# BrainA2-B-11Nov2014.net
KiCad netlist of a schematic drawn in EAGLE
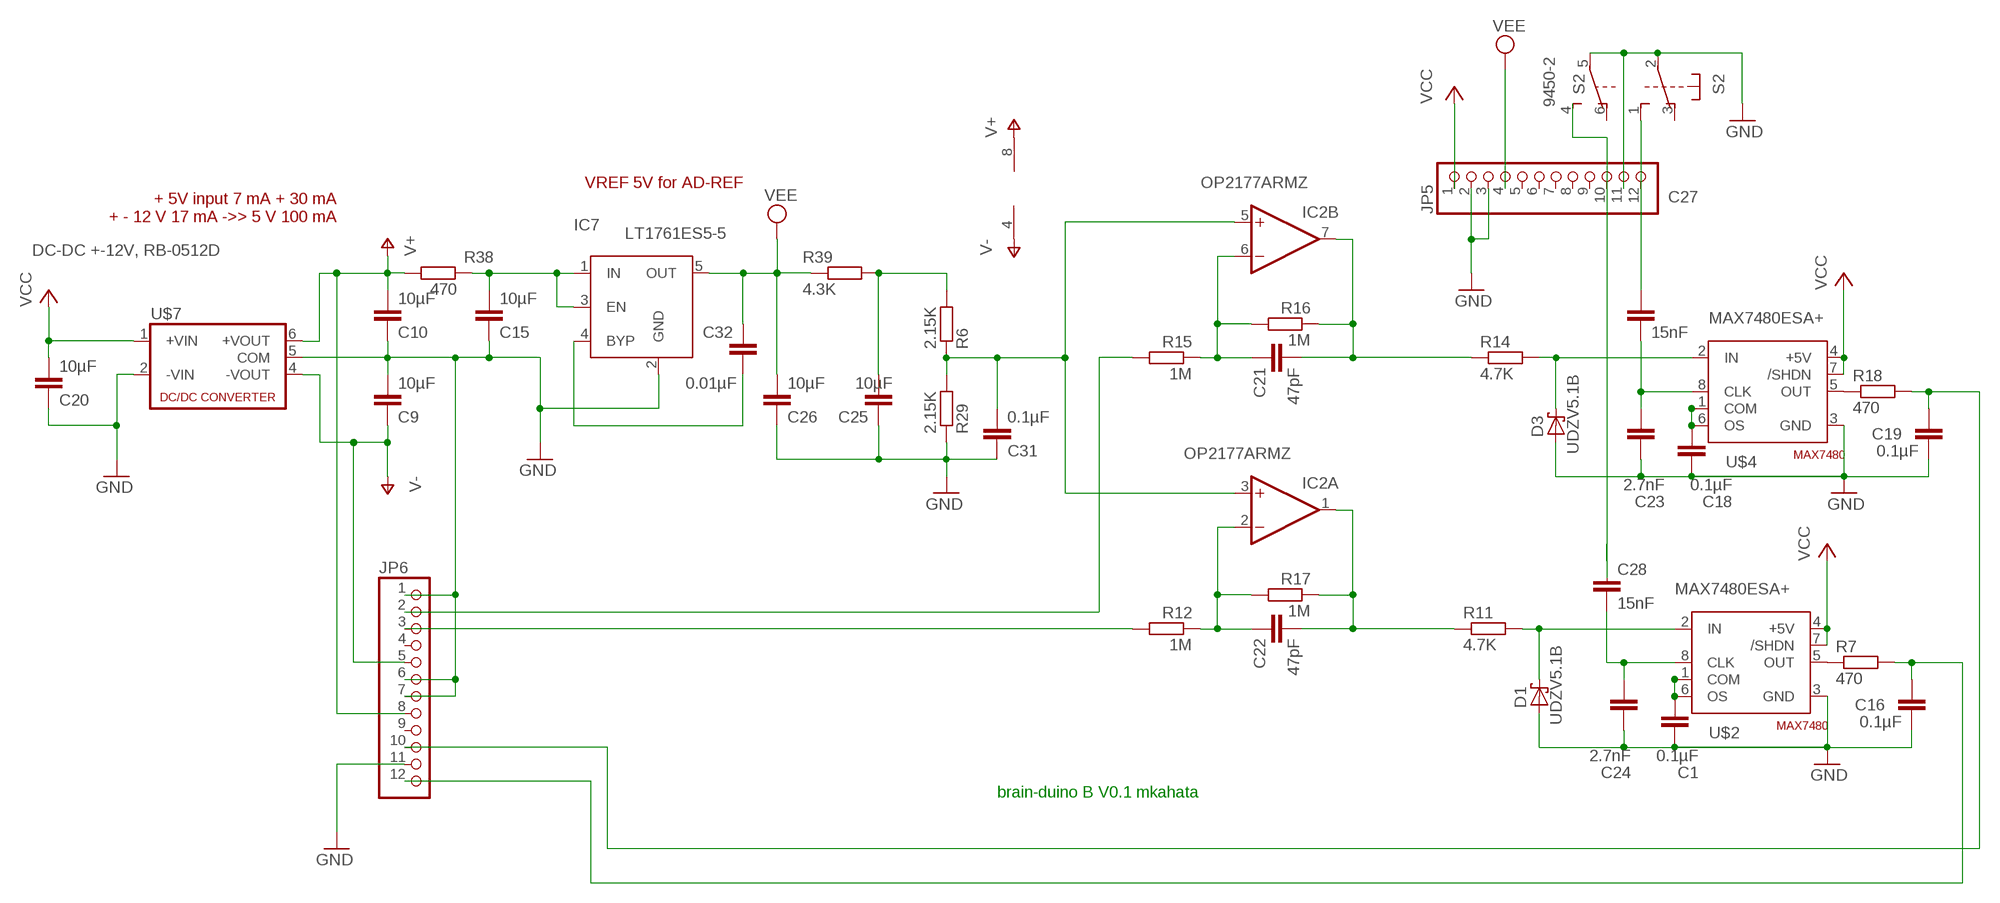
[diagram p0: schematic, sheet 1]

(export (version "E")
  (design (tool "Eeschema 10.0.6"))
  (components
    (comp (ref "C1")
      (value "0.1µF")
      (footprint "eagle-import:C0603")
      (libsource (lib "eagle-import") (part "C-EUC0603"))
    )
    (comp (ref "C9")
      (value "10µF")
      (footprint "eagle-import:C0603")
      (libsource (lib "eagle-import") (part "C-EUC0603"))
    )
    (comp (ref "C10")
      (value "10µF")
      (footprint "eagle-import:C0603")
      (libsource (lib "eagle-import") (part "C-EUC0603"))
    )
    (comp (ref "C15")
      (value "10µF")
      (footprint "eagle-import:C0603")
      (libsource (lib "eagle-import") (part "C-EUC0603"))
    )
    (comp (ref "C16")
      (value "0.1µF")
      (footprint "eagle-import:C0603")
      (libsource (lib "eagle-import") (part "C-EUC0603"))
    )
    (comp (ref "C18")
      (value "0.1µF")
      (footprint "eagle-import:C0603")
      (libsource (lib "eagle-import") (part "C-EUC0603"))
    )
    (comp (ref "C19")
      (value "0.1µF")
      (footprint "eagle-import:C0603")
      (libsource (lib "eagle-import") (part "C-EUC0603"))
    )
    (comp (ref "C20")
      (value "10µF")
      (footprint "eagle-import:C0603")
      (libsource (lib "eagle-import") (part "C-EUC0603"))
    )
    (comp (ref "C21")
      (value "47pF")
      (footprint "eagle-import:C0603")
      (libsource (lib "eagle-import") (part "C-EUC0603"))
    )
    (comp (ref "C22")
      (value "47pF")
      (footprint "eagle-import:C0603")
      (libsource (lib "eagle-import") (part "C-EUC0603"))
    )
    (comp (ref "C23")
      (value "2.7nF")
      (footprint "eagle-import:C0603")
      (libsource (lib "eagle-import") (part "C-EUC0603"))
    )
    (comp (ref "C24")
      (value "2.7nF")
      (footprint "eagle-import:C0603")
      (libsource (lib "eagle-import") (part "C-EUC0603"))
    )
    (comp (ref "C25")
      (value "10µF")
      (footprint "eagle-import:C0603")
      (libsource (lib "eagle-import") (part "C-EUC0603"))
    )
    (comp (ref "C26")
      (value "10µF")
      (footprint "eagle-import:C0603")
      (libsource (lib "eagle-import") (part "C-EUC0603"))
    )
    (comp (ref "C27")
      (value "15nF")
      (footprint "eagle-import:C0603")
      (libsource (lib "eagle-import") (part "C-EUC0603"))
    )
    (comp (ref "C28")
      (value "15nF")
      (footprint "eagle-import:C0603")
      (libsource (lib "eagle-import") (part "C-EUC0603"))
    )
    (comp (ref "C31")
      (value "0.1µF")
      (footprint "eagle-import:C0603")
      (libsource (lib "eagle-import") (part "C-EUC0603"))
    )
    (comp (ref "C32")
      (value "0.01µF")
      (footprint "eagle-import:C0603")
      (libsource (lib "eagle-import") (part "C-EUC0603"))
    )
    (comp (ref "D1")
      (value "UDZV5.1B")
      (footprint "eagle-import:SOD323_ST")
      (libsource (lib "eagle-import") (part "BAT60J"))
    )
    (comp (ref "D3")
      (value "UDZV5.1B")
      (footprint "eagle-import:SOD323_ST")
      (libsource (lib "eagle-import") (part "BAT60J"))
    )
    (comp (ref "IC2")
      (value "OP2177ARMZ")
      (footprint "eagle-import:MSOP08")
      (libsource (lib "eagle-import") (part "OP1277RM"))
    )
    (comp (ref "IC7")
      (value "LT1761ES5-5")
      (footprint "eagle-import:SOT23-5")
      (libsource (lib "eagle-import") (part "MIC5219XX"))
    )
    (comp (ref "JP5")
      (value "PINHD-1X12")
      (footprint "eagle-import:1X12")
      (libsource (lib "eagle-import") (part "PINHD-1X12"))
    )
    (comp (ref "JP6")
      (value "PINHD-1X12")
      (footprint "eagle-import:1X12")
      (libsource (lib "eagle-import") (part "PINHD-1X12"))
    )
    (comp (ref "R6")
      (value "2.15K")
      (footprint "eagle-import:R0603")
      (libsource (lib "eagle-import") (part "R-EU_R0603"))
    )
    (comp (ref "R7")
      (value "470")
      (footprint "eagle-import:R0603")
      (libsource (lib "eagle-import") (part "R-EU_R0603"))
    )
    (comp (ref "R11")
      (value "4.7K")
      (footprint "eagle-import:R0603")
      (libsource (lib "eagle-import") (part "R-EU_R0603"))
    )
    (comp (ref "R12")
      (value "1M")
      (footprint "eagle-import:R0603")
      (libsource (lib "eagle-import") (part "R-EU_R0603"))
    )
    (comp (ref "R14")
      (value "4.7K")
      (footprint "eagle-import:R0603")
      (libsource (lib "eagle-import") (part "R-EU_R0603"))
    )
    (comp (ref "R15")
      (value "1M")
      (footprint "eagle-import:R0603")
      (libsource (lib "eagle-import") (part "R-EU_R0603"))
    )
    (comp (ref "R16")
      (value "1M")
      (footprint "eagle-import:R0603")
      (libsource (lib "eagle-import") (part "R-EU_R0603"))
    )
    (comp (ref "R17")
      (value "1M")
      (footprint "eagle-import:R0603")
      (libsource (lib "eagle-import") (part "R-EU_R0603"))
    )
    (comp (ref "R18")
      (value "470")
      (footprint "eagle-import:R0603")
      (libsource (lib "eagle-import") (part "R-EU_R0603"))
    )
    (comp (ref "R29")
      (value "2.15K")
      (footprint "eagle-import:R0603")
      (libsource (lib "eagle-import") (part "R-EU_R0603"))
    )
    (comp (ref "R38")
      (value "470")
      (footprint "eagle-import:R0603")
      (libsource (lib "eagle-import") (part "R-EU_R0603"))
    )
    (comp (ref "R39")
      (value "4.3K")
      (footprint "eagle-import:R0603")
      (libsource (lib "eagle-import") (part "R-EU_R0603"))
    )
    (comp (ref "S2")
      (value "9450-2")
      (footprint "eagle-import:9450-2")
      (libsource (lib "eagle-import") (part "9450-2"))
    )
    (comp (ref "U$2")
      (value "MAX7480ESA+")
      (footprint "eagle-import:MAX7480")
      (libsource (lib "eagle-import") (part "MAX7480"))
    )
    (comp (ref "U$4")
      (value "MAX7480ESA+")
      (footprint "eagle-import:MAX7480")
      (libsource (lib "eagle-import") (part "MAX7480"))
    )
    (comp (ref "U$7")
      (value "DC-DC +-12V, RB-0512D")
      (footprint "eagle-import:RB-0515D")
      (libsource (lib "eagle-import") (part "RB-0515D"))
    )
  )
  (nets
    (net (code "1") (name "GND") (class "Default")
      (node (ref "C1") (pin "1") (pinfunction "1_1") (pintype "passive"))
      (node (ref "C10") (pin "1") (pinfunction "1_1") (pintype "passive"))
      (node (ref "C15") (pin "1") (pinfunction "1_1") (pintype "passive"))
      (node (ref "C16") (pin "1") (pinfunction "1_1") (pintype "passive"))
      (node (ref "C18") (pin "1") (pinfunction "1_1") (pintype "passive"))
      (node (ref "C19") (pin "1") (pinfunction "1_1") (pintype "passive"))
      (node (ref "C20") (pin "1") (pinfunction "1_1") (pintype "passive"))
      (node (ref "C23") (pin "1") (pinfunction "1_1") (pintype "passive"))
      (node (ref "C24") (pin "1") (pinfunction "1_1") (pintype "passive"))
      (node (ref "C25") (pin "1") (pinfunction "1_1") (pintype "passive"))
      (node (ref "C26") (pin "1") (pinfunction "1_1") (pintype "passive"))
      (node (ref "C31") (pin "1") (pinfunction "1_1") (pintype "passive"))
      (node (ref "C9") (pin "2") (pinfunction "2_2") (pintype "passive"))
      (node (ref "D1") (pin "A") (pinfunction "A_A") (pintype "passive"))
      (node (ref "D3") (pin "A") (pinfunction "A_A") (pintype "passive"))
      (node (ref "IC7") (pin "2") (pinfunction "GND_2") (pintype "power_in"))
      (node (ref "JP5") (pin "11") (pinfunction "11_11") (pintype "passive"))
      (node (ref "JP5") (pin "2") (pinfunction "2_2") (pintype "passive"))
      (node (ref "JP5") (pin "3") (pinfunction "3_3") (pintype "passive"))
      (node (ref "JP6") (pin "1") (pinfunction "1_1") (pintype "passive"))
      (node (ref "JP6") (pin "11") (pinfunction "11_11") (pintype "passive"))
      (node (ref "JP6") (pin "6") (pinfunction "6_6") (pintype "passive"))
      (node (ref "JP6") (pin "7") (pinfunction "7_7") (pintype "passive"))
      (node (ref "R29") (pin "1") (pinfunction "1_1") (pintype "passive"))
      (node (ref "S2") (pin "2") (pinfunction "P_2") (pintype "passive"))
      (node (ref "S2") (pin "5") (pinfunction "P_5") (pintype "passive"))
      (node (ref "U$2") (pin "3") (pinfunction "GND_3") (pintype "power_in"))
      (node (ref "U$4") (pin "3") (pinfunction "GND_3") (pintype "power_in"))
      (node (ref "U$7") (pin "2") (pinfunction "-VIN_2") (pintype "passive"))
      (node (ref "U$7") (pin "5") (pinfunction "COM_5") (pintype "passive"))
    )
    (net (code "2") (name "Net-(C16-Pad2)") (class "Default")
      (node (ref "C16") (pin "2") (pinfunction "2_2") (pintype "passive"))
      (node (ref "JP6") (pin "12") (pinfunction "12_12") (pintype "passive"))
      (node (ref "R7") (pin "2") (pinfunction "2_2") (pintype "passive"))
    )
    (net (code "3") (name "Net-(C19-Pad2)") (class "Default")
      (node (ref "C19") (pin "2") (pinfunction "2_2") (pintype "passive"))
      (node (ref "JP6") (pin "10") (pinfunction "10_10") (pintype "passive"))
      (node (ref "R18") (pin "2") (pinfunction "2_2") (pintype "passive"))
    )
    (net (code "4") (name "Net-(C25-Pad2)") (class "Default")
      (node (ref "C25") (pin "2") (pinfunction "2_2") (pintype "passive"))
      (node (ref "R39") (pin "2") (pinfunction "2_2") (pintype "passive"))
      (node (ref "R6") (pin "2") (pinfunction "2_2") (pintype "passive"))
    )
    (net (code "5") (name "Net-(IC2A-+IN)") (class "Default")
      (node (ref "C31") (pin "2") (pinfunction "2_2") (pintype "passive"))
      (node (ref "IC2") (pin "3") (pinfunction "+IN_3") (pintype "input"))
      (node (ref "IC2") (pin "5") (pinfunction "+IN_5") (pintype "input"))
      (node (ref "R29") (pin "2") (pinfunction "2_2") (pintype "passive"))
      (node (ref "R6") (pin "1") (pinfunction "1_1") (pintype "passive"))
    )
    (net (code "6") (name "Net-(IC2A--IN)") (class "Default")
      (node (ref "C22") (pin "1") (pinfunction "1_1") (pintype "passive"))
      (node (ref "IC2") (pin "2") (pinfunction "-IN_2") (pintype "input"))
      (node (ref "R12") (pin "1") (pinfunction "1_1") (pintype "passive"))
      (node (ref "R17") (pin "2") (pinfunction "2_2") (pintype "passive"))
    )
    (net (code "7") (name "Net-(IC2A-OUT)") (class "Default")
      (node (ref "C22") (pin "2") (pinfunction "2_2") (pintype "passive"))
      (node (ref "IC2") (pin "1") (pinfunction "OUT_1") (pintype "output"))
      (node (ref "R11") (pin "1") (pinfunction "1_1") (pintype "passive"))
      (node (ref "R17") (pin "1") (pinfunction "1_1") (pintype "passive"))
    )
    (net (code "8") (name "Net-(IC2B--IN)") (class "Default")
      (node (ref "C21") (pin "1") (pinfunction "1_1") (pintype "passive"))
      (node (ref "IC2") (pin "6") (pinfunction "-IN_6") (pintype "input"))
      (node (ref "R15") (pin "1") (pinfunction "1_1") (pintype "passive"))
      (node (ref "R16") (pin "2") (pinfunction "2_2") (pintype "passive"))
    )
    (net (code "9") (name "Net-(IC2B-OUT)") (class "Default")
      (node (ref "C21") (pin "2") (pinfunction "2_2") (pintype "passive"))
      (node (ref "IC2") (pin "7") (pinfunction "OUT_7") (pintype "output"))
      (node (ref "R14") (pin "1") (pinfunction "1_1") (pintype "passive"))
      (node (ref "R16") (pin "1") (pinfunction "1_1") (pintype "passive"))
    )
    (net (code "10") (name "Net-(IC7-BYP)") (class "Default")
      (node (ref "C32") (pin "1") (pinfunction "1_1") (pintype "passive"))
      (node (ref "IC7") (pin "4") (pinfunction "BYP_4") (pintype "passive"))
    )
    (net (code "11") (name "Net-(IC7-EN)") (class "Default")
      (node (ref "C15") (pin "2") (pinfunction "2_2") (pintype "passive"))
      (node (ref "IC7") (pin "1") (pinfunction "IN_1") (pintype "input"))
      (node (ref "IC7") (pin "3") (pinfunction "EN_3") (pintype "input"))
      (node (ref "R38") (pin "2") (pinfunction "2_2") (pintype "passive"))
    )
    (net (code "12") (name "Net-(JP6-Pad2)") (class "Default")
      (node (ref "JP6") (pin "2") (pinfunction "2_2") (pintype "passive"))
      (node (ref "R15") (pin "2") (pinfunction "2_2") (pintype "passive"))
    )
    (net (code "13") (name "Net-(JP6-Pad3)") (class "Default")
      (node (ref "JP6") (pin "3") (pinfunction "3_3") (pintype "passive"))
      (node (ref "R12") (pin "2") (pinfunction "2_2") (pintype "passive"))
    )
    (net (code "14") (name "Net-(S2A-S)") (class "Default")
      (node (ref "C27") (pin "1") (pinfunction "1_1") (pintype "passive"))
      (node (ref "JP5") (pin "12") (pinfunction "12_12") (pintype "passive"))
      (node (ref "S2") (pin "1") (pinfunction "S_1") (pintype "passive"))
    )
    (net (code "15") (name "Net-(S2B-S)") (class "Default")
      (node (ref "C28") (pin "1") (pinfunction "1_1") (pintype "passive"))
      (node (ref "JP5") (pin "10") (pinfunction "10_10") (pintype "passive"))
      (node (ref "S2") (pin "4") (pinfunction "S_4") (pintype "passive"))
    )
    (net (code "16") (name "Net-(U$2-CLK)") (class "Default")
      (node (ref "C24") (pin "2") (pinfunction "2_2") (pintype "passive"))
      (node (ref "C28") (pin "2") (pinfunction "2_2") (pintype "passive"))
      (node (ref "U$2") (pin "8") (pinfunction "CLK_8") (pintype "input"))
    )
    (net (code "17") (name "Net-(U$2-COM)") (class "Default")
      (node (ref "C1") (pin "2") (pinfunction "2_2") (pintype "passive"))
      (node (ref "U$2") (pin "1") (pinfunction "COM_1") (pintype "input"))
      (node (ref "U$2") (pin "6") (pinfunction "OS_6") (pintype "passive"))
    )
    (net (code "18") (name "Net-(U$2-IN)") (class "Default")
      (node (ref "D1") (pin "C") (pinfunction "C_C") (pintype "passive"))
      (node (ref "R11") (pin "2") (pinfunction "2_2") (pintype "passive"))
      (node (ref "U$2") (pin "2") (pinfunction "IN_2") (pintype "input"))
    )
    (net (code "19") (name "Net-(U$2-OUT)") (class "Default")
      (node (ref "R7") (pin "1") (pinfunction "1_1") (pintype "passive"))
      (node (ref "U$2") (pin "5") (pinfunction "OUT_5") (pintype "input"))
    )
    (net (code "20") (name "Net-(U$4-CLK)") (class "Default")
      (node (ref "C23") (pin "2") (pinfunction "2_2") (pintype "passive"))
      (node (ref "C27") (pin "2") (pinfunction "2_2") (pintype "passive"))
      (node (ref "U$4") (pin "8") (pinfunction "CLK_8") (pintype "input"))
    )
    (net (code "21") (name "Net-(U$4-COM)") (class "Default")
      (node (ref "C18") (pin "2") (pinfunction "2_2") (pintype "passive"))
      (node (ref "U$4") (pin "1") (pinfunction "COM_1") (pintype "input"))
      (node (ref "U$4") (pin "6") (pinfunction "OS_6") (pintype "passive"))
    )
    (net (code "22") (name "Net-(U$4-IN)") (class "Default")
      (node (ref "D3") (pin "C") (pinfunction "C_C") (pintype "passive"))
      (node (ref "R14") (pin "2") (pinfunction "2_2") (pintype "passive"))
      (node (ref "U$4") (pin "2") (pinfunction "IN_2") (pintype "input"))
    )
    (net (code "23") (name "Net-(U$4-OUT)") (class "Default")
      (node (ref "R18") (pin "1") (pinfunction "1_1") (pintype "passive"))
      (node (ref "U$4") (pin "5") (pinfunction "OUT_5") (pintype "input"))
    )
    (net (code "24") (name "V+") (class "Default")
      (node (ref "C10") (pin "2") (pinfunction "2_2") (pintype "passive"))
      (node (ref "IC2") (pin "8") (pinfunction "V+_8") (pintype "power_in"))
      (node (ref "JP6") (pin "8") (pinfunction "8_8") (pintype "passive"))
      (node (ref "R38") (pin "1") (pinfunction "1_1") (pintype "passive"))
      (node (ref "U$7") (pin "6") (pinfunction "+VOUT_6") (pintype "passive"))
    )
    (net (code "25") (name "V-") (class "Default")
      (node (ref "C9") (pin "1") (pinfunction "1_1") (pintype "passive"))
      (node (ref "IC2") (pin "4") (pinfunction "V-_4") (pintype "power_in"))
      (node (ref "JP6") (pin "5") (pinfunction "5_5") (pintype "passive"))
      (node (ref "U$7") (pin "4") (pinfunction "-VOUT_4") (pintype "passive"))
    )
    (net (code "26") (name "VCC") (class "Default")
      (node (ref "C20") (pin "2") (pinfunction "2_2") (pintype "passive"))
      (node (ref "JP5") (pin "1") (pinfunction "1_1") (pintype "passive"))
      (node (ref "U$2") (pin "4") (pinfunction "+5V_4") (pintype "power_in"))
      (node (ref "U$2") (pin "7") (pinfunction "/SHDN_7") (pintype "input"))
      (node (ref "U$4") (pin "4") (pinfunction "+5V_4") (pintype "power_in"))
      (node (ref "U$4") (pin "7") (pinfunction "/SHDN_7") (pintype "input"))
      (node (ref "U$7") (pin "1") (pinfunction "+VIN_1") (pintype "passive"))
    )
    (net (code "27") (name "VEE") (class "Default")
      (node (ref "C26") (pin "2") (pinfunction "2_2") (pintype "passive"))
      (node (ref "C32") (pin "2") (pinfunction "2_2") (pintype "passive"))
      (node (ref "IC7") (pin "5") (pinfunction "OUT_5") (pintype "output"))
      (node (ref "JP5") (pin "4") (pinfunction "4_4") (pintype "passive"))
      (node (ref "R39") (pin "1") (pinfunction "1_1") (pintype "passive"))
    )
    (net (code "28") (name "unconnected-(JP5-Pad5)") (class "Default")
      (node (ref "JP5") (pin "5") (pinfunction "5_5") (pintype "passive"))
    )
    (net (code "29") (name "unconnected-(JP5-Pad6)") (class "Default")
      (node (ref "JP5") (pin "6") (pinfunction "6_6") (pintype "passive"))
    )
    (net (code "30") (name "unconnected-(JP5-Pad7)") (class "Default")
      (node (ref "JP5") (pin "7") (pinfunction "7_7") (pintype "passive"))
    )
    (net (code "31") (name "unconnected-(JP5-Pad8)") (class "Default")
      (node (ref "JP5") (pin "8") (pinfunction "8_8") (pintype "passive"))
    )
    (net (code "32") (name "unconnected-(JP5-Pad9)") (class "Default")
      (node (ref "JP5") (pin "9") (pinfunction "9_9") (pintype "passive"))
    )
    (net (code "33") (name "unconnected-(JP6-Pad4)") (class "Default")
      (node (ref "JP6") (pin "4") (pinfunction "4_4") (pintype "passive"))
    )
    (net (code "34") (name "unconnected-(JP6-Pad9)") (class "Default")
      (node (ref "JP6") (pin "9") (pinfunction "9_9") (pintype "passive"))
    )
    (net (code "35") (name "unconnected-(S2A-O-Pad3)") (class "Default")
      (node (ref "S2") (pin "3") (pinfunction "O_3") (pintype "passive"))
    )
    (net (code "36") (name "unconnected-(S2B-O-Pad6)") (class "Default")
      (node (ref "S2") (pin "6") (pinfunction "O_6") (pintype "passive"))
    )
  )
)
